# MINIMP3.net
KiCad netlist of a schematic drawn in Altium Designer
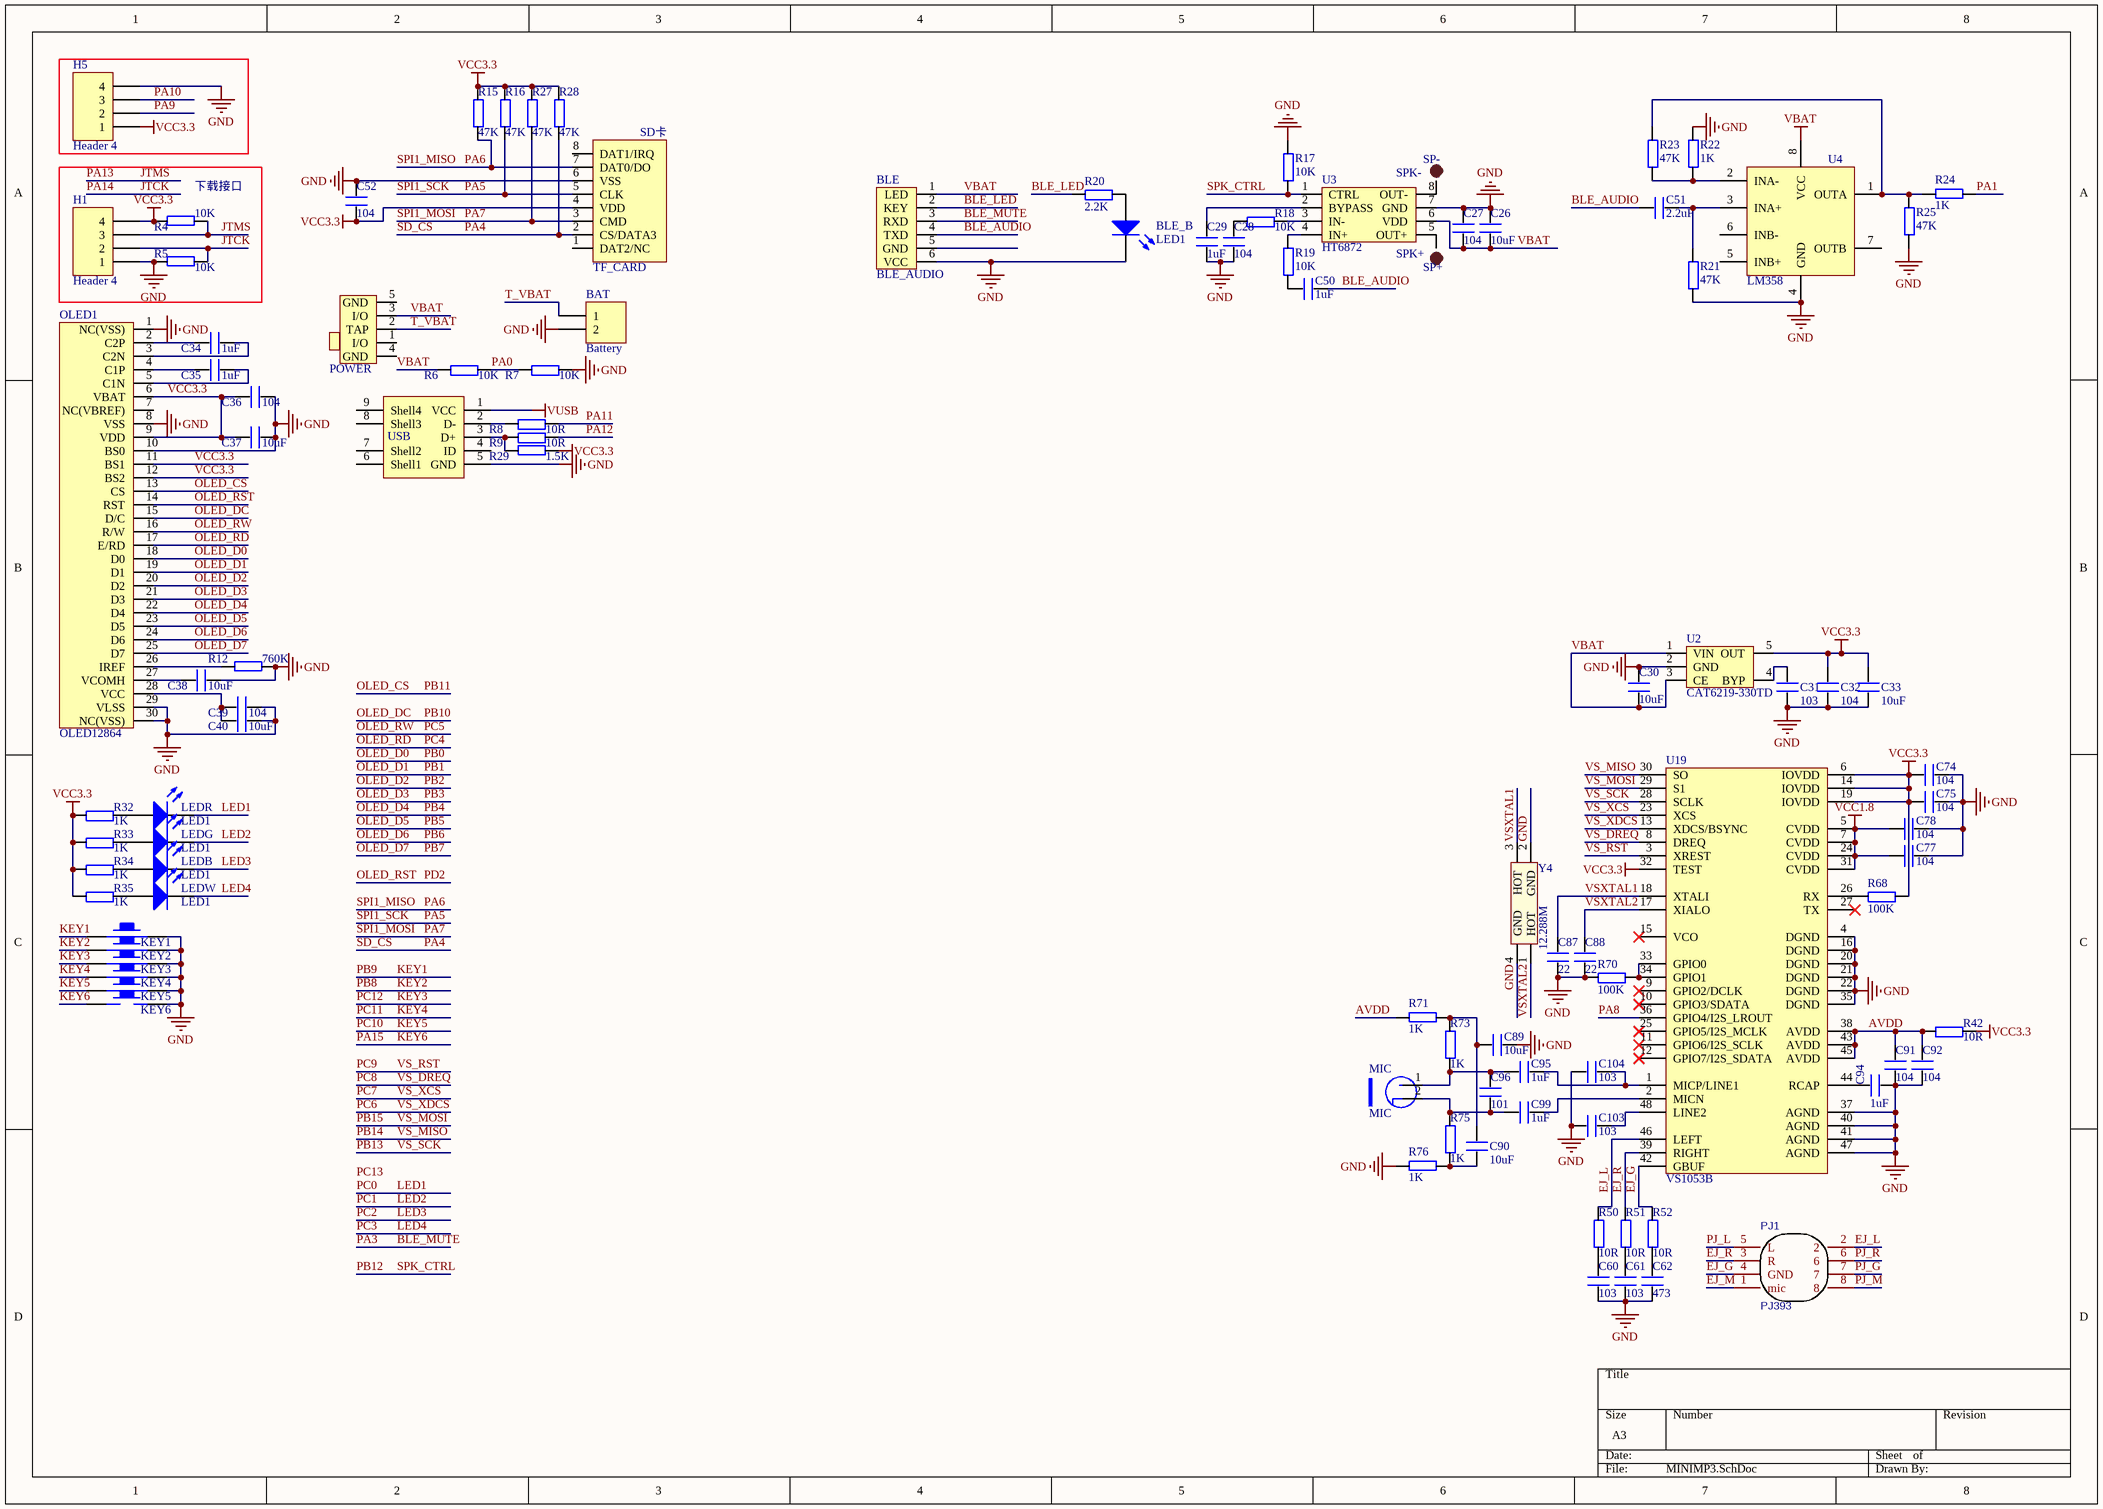
[diagram p0: MINIMP3.SchDoc]

(export (version "E")
  (design (tool "Eeschema 10.0.6"))
  (components
    (comp (ref "BAT")
      (value "Battery")
      (footprint "HDR2.54-LI-2P")
      (description "Header, 2-Pin")
      (fields (field (name "PUBLISHER") "Altium Limited"))
      (libsource (lib "WarShip V3 STM32103封装库") (part "Header 2"))
    )
    (comp (ref "BLE")
      (value "BLE_AUDIO")
      (footprint "HEAD6")
      (description "ATK-HC05")
      (libsource (lib "阿波罗STM32F4&F7&H7底板封装库") (part "ATK-HC05"))
    )
    (comp (ref "BLE_B")
      (value "LED1")
      (footprint "LED 0805B")
      (description "Typical RED, GREEN, YELLOW, AMBER GaAs LED")
      (fields (field (name "PUBLISHER") "Altium Limited"))
      (libsource (lib "阿波罗STM32F4&F7底板封装库") (part "LED2"))
    )
    (comp (ref "C26")
      (value "10uF")
      (footprint "C 0603_M")
      (libsource (lib "WarShip V3 STM32103封装库") (part "C"))
    )
    (comp (ref "C27")
      (value "104")
      (footprint "C 0603_M")
      (libsource (lib "WarShip V3 STM32103封装库") (part "C"))
    )
    (comp (ref "C28")
      (value "104")
      (footprint "C 0603_M")
      (libsource (lib "WarShip V3 STM32103封装库") (part "C"))
    )
    (comp (ref "C29")
      (value "1uF")
      (footprint "C 0603_M")
      (libsource (lib "WarShip V3 STM32103封装库") (part "C"))
    )
    (comp (ref "C30")
      (value "10uF")
      (footprint "C 0603_M")
      (libsource (lib "WarShip V3 STM32103封装库") (part "C"))
    )
    (comp (ref "C31")
      (value "103")
      (footprint "C 0603_M")
      (libsource (lib "WarShip V3 STM32103封装库") (part "C"))
    )
    (comp (ref "C32")
      (value "104")
      (footprint "C 0603_M")
      (libsource (lib "WarShip V3 STM32103封装库") (part "C"))
    )
    (comp (ref "C33")
      (value "10uF")
      (footprint "C 0603_M")
      (libsource (lib "WarShip V3 STM32103封装库") (part "C"))
    )
    (comp (ref "C34")
      (value "1uF")
      (footprint "C 0603_M")
      (libsource (lib "WarShip V3 STM32103封装库") (part "C"))
    )
    (comp (ref "C35")
      (value "1uF")
      (footprint "C 0603_M")
      (libsource (lib "WarShip V3 STM32103封装库") (part "C"))
    )
    (comp (ref "C36")
      (value "104")
      (footprint "C 0603_M")
      (libsource (lib "WarShip V3 STM32103封装库") (part "C"))
    )
    (comp (ref "C37")
      (value "10uF")
      (footprint "C 0603_M")
      (libsource (lib "WarShip V3 STM32103封装库") (part "C"))
    )
    (comp (ref "C38")
      (value "10uF")
      (footprint "C 0603_M")
      (libsource (lib "WarShip V3 STM32103封装库") (part "C"))
    )
    (comp (ref "C39")
      (value "104")
      (footprint "C 0603_M")
      (libsource (lib "WarShip V3 STM32103封装库") (part "C"))
    )
    (comp (ref "C40")
      (value "10uF")
      (footprint "C 0603_M")
      (libsource (lib "WarShip V3 STM32103封装库") (part "C"))
    )
    (comp (ref "C50") (value "1uF") (footprint "C 0603_M") (libsource (lib "MYCOMLIB") (part "C")))
    (comp (ref "C51") (value "2.2uF") (footprint "C 0603_M") (libsource (lib "MYCOMLIB") (part "C")))
    (comp (ref "C52")
      (value "104")
      (footprint "C 0603_M")
      (libsource (lib "WarShip V3 STM32103封装库") (part "C"))
    )
    (comp (ref "C60")
      (value "103")
      (footprint "C 0603_M")
      (libsource (lib "WarShip V3 STM32103封装库") (part "C"))
    )
    (comp (ref "C61")
      (value "103")
      (footprint "C 0603_M")
      (libsource (lib "WarShip V3 STM32103封装库") (part "C"))
    )
    (comp (ref "C62")
      (value "473")
      (footprint "C 0603_M")
      (libsource (lib "WarShip V3 STM32103封装库") (part "C"))
    )
    (comp (ref "C74") (value "104") (footprint "C 0603_M") (libsource (lib "ATK-VS1053 MP3") (part "C")))
    (comp (ref "C75") (value "104") (footprint "C 0603_M") (libsource (lib "ATK-VS1053 MP3") (part "C")))
    (comp (ref "C77") (value "104") (footprint "C 0603_M") (libsource (lib "ATK-VS1053 MP3") (part "C")))
    (comp (ref "C78") (value "104") (footprint "C 0603_M") (libsource (lib "ATK-VS1053 MP3") (part "C")))
    (comp (ref "C87") (value "22") (footprint "C 0603_M") (libsource (lib "ATK-VS1053 MP3") (part "C")))
    (comp (ref "C88") (value "22") (footprint "C 0603_M") (libsource (lib "ATK-VS1053 MP3") (part "C")))
    (comp (ref "C89")
      (value "10uF")
      (footprint "C 0805_M")
      (libsource (lib "WarShip V3 STM32103封装库") (part "C"))
    )
    (comp (ref "C90")
      (value "10uF")
      (footprint "C 0805_M")
      (libsource (lib "WarShip V3 STM32103封装库") (part "C"))
    )
    (comp (ref "C91") (value "104") (footprint "C 0603_M") (libsource (lib "ATK-VS1053 MP3") (part "C")))
    (comp (ref "C92") (value "104") (footprint "C 0603_M") (libsource (lib "ATK-VS1053 MP3") (part "C")))
    (comp (ref "C94") (value "1uF") (footprint "C 0603_M") (libsource (lib "ATK-VS1053 MP3") (part "C")))
    (comp (ref "C95")
      (value "1uF")
      (footprint "C 0603_M")
      (libsource (lib "WarShip V3 STM32103封装库") (part "C"))
    )
    (comp (ref "C96")
      (value "101")
      (footprint "C 0603_M")
      (libsource (lib "WarShip V3 STM32103封装库") (part "C"))
    )
    (comp (ref "C99")
      (value "1uF")
      (footprint "C 0603_M")
      (libsource (lib "WarShip V3 STM32103封装库") (part "C"))
    )
    (comp (ref "C103")
      (value "103")
      (footprint "C 0603_M")
      (libsource (lib "WarShip V3 STM32103封装库") (part "C"))
    )
    (comp (ref "C104")
      (value "103")
      (footprint "C 0603_M")
      (libsource (lib "WarShip V3 STM32103封装库") (part "C"))
    )
    (comp (ref "H1")
      (value "Header 4")
      (footprint "HDR2.54-LI-4P")
      (description "Header, 4-Pin")
      (fields (field (name "PUBLISHER") "Altium Limited"))
      (libsource (lib "WarShip V3 STM32103封装库") (part "Header 4"))
    )
    (comp (ref "H5")
      (value "Header 4")
      (footprint "HDR2.54-LI-4P")
      (description "Header, 4-Pin")
      (fields (field (name "PUBLISHER") "Altium Limited"))
      (libsource (lib "WarShip V3 STM32103封装库") (part "Header 4"))
    )
    (comp (ref "KEY1")
      (value "KEY_M")
      (footprint "KEY-SOP324225")
      (libsource (lib "WarShip V3 STM32103封装库") (part "KEY_M"))
    )
    (comp (ref "KEY2")
      (value "KEY_M")
      (footprint "KEY-SOP324225")
      (libsource (lib "WarShip V3 STM32103封装库") (part "KEY_M"))
    )
    (comp (ref "KEY3")
      (value "KEY_M")
      (footprint "KEY-SOP324225")
      (libsource (lib "WarShip V3 STM32103封装库") (part "KEY_M"))
    )
    (comp (ref "KEY4")
      (value "KEY_M")
      (footprint "KEY-SOP324225")
      (libsource (lib "WarShip V3 STM32103封装库") (part "KEY_M"))
    )
    (comp (ref "KEY5")
      (value "KEY_M")
      (footprint "KEY-SOP324225")
      (libsource (lib "WarShip V3 STM32103封装库") (part "KEY_M"))
    )
    (comp (ref "KEY6")
      (value "KEY_M")
      (footprint "KEY-SOP324225")
      (libsource (lib "WarShip V3 STM32103封装库") (part "KEY_M"))
    )
    (comp (ref "LEDB")
      (value "LED1")
      (footprint "LED 0805B")
      (description "Typical RED, GREEN, YELLOW, AMBER GaAs LED")
      (fields (field (name "PUBLISHER") "Altium Limited"))
      (libsource (lib "阿波罗STM32F4&F7底板封装库") (part "LED2"))
    )
    (comp (ref "LEDG")
      (value "LED1")
      (footprint "LED 0805B")
      (description "Typical RED, GREEN, YELLOW, AMBER GaAs LED")
      (fields (field (name "PUBLISHER") "Altium Limited"))
      (libsource (lib "阿波罗STM32F4&F7底板封装库") (part "LED2"))
    )
    (comp (ref "LEDR")
      (value "LED1")
      (footprint "LED 0805B")
      (description "Typical RED, GREEN, YELLOW, AMBER GaAs LED")
      (fields (field (name "PUBLISHER") "Altium Limited"))
      (libsource (lib "阿波罗STM32F4&F7底板封装库") (part "LED2"))
    )
    (comp (ref "LEDW")
      (value "LED1")
      (footprint "LED 0805B")
      (description "Typical RED, GREEN, YELLOW, AMBER GaAs LED")
      (fields (field (name "PUBLISHER") "Altium Limited"))
      (libsource (lib "阿波罗STM32F4&F7底板封装库") (part "LED2"))
    )
    (comp (ref "MIC") (value "MIC") (footprint "MIC-6022") (libsource (lib "ATK-VS1053 MP3") (part "MIC")))
    (comp (ref "OLED1")
      (value "OLED12864")
      (footprint "OLED_0.96")
      (libsource (lib "OLED模块封装库") (part "OLED12864"))
    )
    (comp (ref "PJ1")
      (value "PJ393")
      (footprint "PJ393")
      (fields
        (field (name "BOM_MANUFACTURER PART") "?")
        (field (name "CONTRIBUTOR") "infinite_possibilities")
      )
      (libsource (lib "PJ393") (part "PJ393"))
    )
    (comp (ref "POWER")
      (value "BUTTON_DIP3")
      (footprint "MSK-12C01-07")
      (description "拨动开关SS-12F44")
      (libsource (lib "Pandora_STM32L4_Board_V2.4") (part "BUTTON_DIP3"))
    )
    (comp (ref "R4")
      (value "10K")
      (footprint "R 0603_M")
      (libsource (lib "WarShip V3 STM32103封装库") (part "R"))
    )
    (comp (ref "R5")
      (value "10K")
      (footprint "R 0603_M")
      (libsource (lib "WarShip V3 STM32103封装库") (part "R"))
    )
    (comp (ref "R6")
      (value "10K")
      (footprint "R 0603_M")
      (libsource (lib "WarShip V3 STM32103封装库") (part "R"))
    )
    (comp (ref "R7")
      (value "10K")
      (footprint "R 0603_M")
      (libsource (lib "WarShip V3 STM32103封装库") (part "R"))
    )
    (comp (ref "R8")
      (value "10R")
      (footprint "R 0603_M")
      (libsource (lib "WarShip V3 STM32103封装库") (part "R"))
    )
    (comp (ref "R9")
      (value "10R")
      (footprint "R 0603_M")
      (libsource (lib "WarShip V3 STM32103封装库") (part "R"))
    )
    (comp (ref "R12")
      (value "760K")
      (footprint "R 0603_M")
      (libsource (lib "WarShip V3 STM32103封装库") (part "R"))
    )
    (comp (ref "R15")
      (value "47K")
      (footprint "R 0603_M")
      (libsource (lib "WarShip V3 STM32103封装库") (part "R"))
    )
    (comp (ref "R16")
      (value "47K")
      (footprint "R 0603_M")
      (libsource (lib "WarShip V3 STM32103封装库") (part "R"))
    )
    (comp (ref "R17") (value "10K") (footprint "R 0603_M") (libsource (lib "ALIENTEK_COMPONENT") (part "R")))
    (comp (ref "R18") (value "10K") (footprint "R 0603_M") (libsource (lib "ALIENTEK_COMPONENT") (part "R")))
    (comp (ref "R19") (value "10K") (footprint "R 0603_M") (libsource (lib "ALIENTEK_COMPONENT") (part "R")))
    (comp (ref "R20")
      (value "2.2K")
      (footprint "R 0603_M")
      (libsource (lib "WarShip V3 STM32103封装库") (part "R"))
    )
    (comp (ref "R21") (value "47K") (footprint "R 0603_M") (libsource (lib "ALIENTEK_COMPONENT") (part "R")))
    (comp (ref "R22") (value "1K") (footprint "R 0603_M") (libsource (lib "ALIENTEK_COMPONENT") (part "R")))
    (comp (ref "R23") (value "47K") (footprint "R 0603_M") (libsource (lib "ALIENTEK_COMPONENT") (part "R")))
    (comp (ref "R24") (value "1K") (footprint "R 0603_M") (libsource (lib "ALIENTEK_COMPONENT") (part "R")))
    (comp (ref "R25") (value "47K") (footprint "R 0603_M") (libsource (lib "ALIENTEK_COMPONENT") (part "R")))
    (comp (ref "R27")
      (value "47K")
      (footprint "R 0603_M")
      (libsource (lib "WarShip V3 STM32103封装库") (part "R"))
    )
    (comp (ref "R28")
      (value "47K")
      (footprint "R 0603_M")
      (libsource (lib "WarShip V3 STM32103封装库") (part "R"))
    )
    (comp (ref "R29")
      (value "1.5K")
      (footprint "R 0603_M")
      (libsource (lib "WarShip V3 STM32103封装库") (part "R"))
    )
    (comp (ref "R32")
      (value "1K")
      (footprint "R 0603_M")
      (libsource (lib "WarShip V3 STM32103封装库") (part "R"))
    )
    (comp (ref "R33")
      (value "1K")
      (footprint "R 0603_M")
      (libsource (lib "WarShip V3 STM32103封装库") (part "R"))
    )
    (comp (ref "R34")
      (value "1K")
      (footprint "R 0603_M")
      (libsource (lib "WarShip V3 STM32103封装库") (part "R"))
    )
    (comp (ref "R35")
      (value "1K")
      (footprint "R 0603_M")
      (libsource (lib "WarShip V3 STM32103封装库") (part "R"))
    )
    (comp (ref "R42") (value "10R") (footprint "R 0603_M") (libsource (lib "ATK-VS1053 MP3") (part "R")))
    (comp (ref "R50")
      (value "10R")
      (footprint "R 0603_M")
      (libsource (lib "WarShip V3 STM32103封装库") (part "R"))
    )
    (comp (ref "R51")
      (value "10R")
      (footprint "R 0603_M")
      (libsource (lib "WarShip V3 STM32103封装库") (part "R"))
    )
    (comp (ref "R52")
      (value "10R")
      (footprint "R 0603_M")
      (libsource (lib "WarShip V3 STM32103封装库") (part "R"))
    )
    (comp (ref "R68") (value "100K") (footprint "R 0603_M") (libsource (lib "ATK-VS1053 MP3") (part "R")))
    (comp (ref "R70") (value "100K") (footprint "R 0603_M") (libsource (lib "ATK-VS1053 MP3") (part "R")))
    (comp (ref "R71")
      (value "1K")
      (footprint "R 0603_M")
      (libsource (lib "WarShip V3 STM32103封装库") (part "R"))
    )
    (comp (ref "R73")
      (value "1K")
      (footprint "R 0603_M")
      (libsource (lib "WarShip V3 STM32103封装库") (part "R"))
    )
    (comp (ref "R75")
      (value "1K")
      (footprint "R 0603_M")
      (libsource (lib "WarShip V3 STM32103封装库") (part "R"))
    )
    (comp (ref "R76")
      (value "1K")
      (footprint "R 0603_M")
      (libsource (lib "WarShip V3 STM32103封装库") (part "R"))
    )
    (comp (ref "SP+")
      (value "SPK+")
      (footprint "TP-1.5")
      (description "测试点")
      (libsource (lib "ALIENTEK_COMPONENT") (part "TEST-POINT"))
    )
    (comp (ref "SP-")
      (value "SPK-")
      (footprint "TP-1.5")
      (description "测试点")
      (libsource (lib "ALIENTEK_COMPONENT") (part "TEST-POINT"))
    )
    (comp (ref "TF_CARD")
      (value "SD-MICRO-TF")
      (footprint "SD-MICRO-TF")
      (description "SD,MICRO,TF")
      (libsource (lib "Pandora_STM32L4_Board_V2.4") (part "SD-MICRO-TF"))
    )
    (comp (ref "U2")
      (value "CAT6219-330TD")
      (footprint "SOT23-5N")
      (description "3.3V 500mA LDO")
      (libsource (lib "STM32H743核心板封装库") (part "CAT6219-330TD"))
    )
    (comp (ref "U3")
      (value "HT6872")
      (footprint "SOP8_N")
      (description "HT6871")
      (libsource (lib "WarShip V3 STM32103封装库") (part "HT6871"))
    )
    (comp (ref "U4") (value "LM358") (footprint "SOP8_N") (libsource (lib "tp4056") (part "Component_2")))
    (comp (ref "U19")
      (value "VS1053B")
      (footprint "LQFP-48N")
      (libsource (lib "ATK-VS1053 MP3") (part "VS1053"))
    )
    (comp (ref "USB")
      (value "J-MICRO-USB-5S")
      (footprint "USB-AB-5S")
      (description "Micro USB 5.9有柱脚长1.25加长针")
      (libsource (lib "Pandora_STM32L4_Board_V2.4") (part "J-MICRO-USB-5S"))
    )
    (comp (ref "Y4")
      (value "12.288M")
      (footprint "OSC 3225-4P")
      (description "3225贴片无源晶振")
      (libsource (lib "STM32F767核心板封装库") (part "XTAL_3225"))
    )
  )
  (nets
    (net (code "1") (name "/AVDD") (class "Default")
      (node (ref "C91") (pin "2") (pintype "passive"))
      (node (ref "C92") (pin "2") (pintype "passive"))
      (node (ref "R42") (pin "1") (pintype "passive"))
      (node (ref "R71") (pin "2") (pintype "passive"))
      (node (ref "U19") (pin "38") (pinfunction "AVDD_38") (pintype "passive"))
      (node (ref "U19") (pin "43") (pinfunction "AVDD_43") (pintype "passive"))
      (node (ref "U19") (pin "45") (pinfunction "AVDD_45") (pintype "passive"))
    )
    (net (code "2") (name "/BLE_AUDIO") (class "Default")
      (node (ref "BLE") (pin "4") (pinfunction "TXD_4") (pintype "passive"))
      (node (ref "C50") (pin "2") (pintype "passive"))
      (node (ref "C51") (pin "1") (pintype "passive"))
    )
    (net (code "3") (name "/BLE_LED") (class "Default")
      (node (ref "BLE") (pin "2") (pinfunction "KEY_2") (pintype "passive"))
      (node (ref "R20") (pin "1") (pintype "passive"))
    )
    (net (code "4") (name "/BLE_MUTE") (class "Default")
      (node (ref "BLE") (pin "3") (pinfunction "RXD_3") (pintype "passive"))
    )
    (net (code "5") (name "/EJ_G") (class "Default")
      (node (ref "PJ1") (pin "4") (pinfunction "GND_4") (pintype "passive"))
      (node (ref "R52") (pin "2") (pintype "passive"))
      (node (ref "U19") (pin "42") (pinfunction "GBUF_42") (pintype "passive"))
    )
    (net (code "6") (name "/EJ_L") (class "Default")
      (node (ref "PJ1") (pin "2") (pinfunction "2_2") (pintype "passive"))
      (node (ref "R50") (pin "2") (pintype "passive"))
      (node (ref "U19") (pin "46") (pinfunction "LEFT_46") (pintype "passive"))
    )
    (net (code "7") (name "/EJ_M") (class "Default")
      (node (ref "PJ1") (pin "1") (pinfunction "mic_1") (pintype "passive"))
    )
    (net (code "8") (name "/EJ_R") (class "Default")
      (node (ref "PJ1") (pin "3") (pinfunction "R_3") (pintype "passive"))
      (node (ref "R51") (pin "2") (pintype "passive"))
      (node (ref "U19") (pin "39") (pinfunction "RIGHT_39") (pintype "passive"))
    )
    (net (code "9") (name "/JTCK") (class "Default")
      (node (ref "H1") (pin "2") (pinfunction "2_2") (pintype "passive"))
      (node (ref "R5") (pin "1") (pintype "passive"))
    )
    (net (code "10") (name "/JTMS") (class "Default")
      (node (ref "H1") (pin "3") (pinfunction "3_3") (pintype "passive"))
      (node (ref "R4") (pin "1") (pintype "passive"))
    )
    (net (code "11") (name "/KEY1") (class "Default")
      (node (ref "KEY1") (pin "1") (pinfunction "1_1") (pintype "passive"))
    )
    (net (code "12") (name "/KEY2") (class "Default")
      (node (ref "KEY2") (pin "1") (pinfunction "1_1") (pintype "passive"))
    )
    (net (code "13") (name "/KEY3") (class "Default")
      (node (ref "KEY3") (pin "1") (pinfunction "1_1") (pintype "passive"))
    )
    (net (code "14") (name "/KEY4") (class "Default")
      (node (ref "KEY4") (pin "1") (pinfunction "1_1") (pintype "passive"))
    )
    (net (code "15") (name "/KEY5") (class "Default")
      (node (ref "KEY5") (pin "1") (pinfunction "1_1") (pintype "passive"))
    )
    (net (code "16") (name "/KEY6") (class "Default")
      (node (ref "KEY6") (pin "1") (pinfunction "1_1") (pintype "passive"))
    )
    (net (code "17") (name "/LED1") (class "Default")
      (node (ref "LEDR") (pin "2") (pinfunction "K_2") (pintype "passive"))
    )
    (net (code "18") (name "/LED2") (class "Default")
      (node (ref "LEDG") (pin "2") (pinfunction "K_2") (pintype "passive"))
    )
    (net (code "19") (name "/LED3") (class "Default")
      (node (ref "LEDB") (pin "2") (pinfunction "K_2") (pintype "passive"))
    )
    (net (code "20") (name "/LED4") (class "Default")
      (node (ref "LEDW") (pin "2") (pinfunction "K_2") (pintype "passive"))
    )
    (net (code "21") (name "/OLED_CS") (class "Default")
      (node (ref "OLED1") (pin "13") (pinfunction "CS_13") (pintype "passive"))
    )
    (net (code "22") (name "/OLED_D0") (class "Default")
      (node (ref "OLED1") (pin "18") (pinfunction "D0_18") (pintype "passive"))
    )
    (net (code "23") (name "/OLED_D1") (class "Default")
      (node (ref "OLED1") (pin "19") (pinfunction "D1_19") (pintype "passive"))
    )
    (net (code "24") (name "/OLED_D2") (class "Default")
      (node (ref "OLED1") (pin "20") (pinfunction "D2_20") (pintype "passive"))
    )
    (net (code "25") (name "/OLED_D3") (class "Default")
      (node (ref "OLED1") (pin "21") (pinfunction "D3_21") (pintype "passive"))
    )
    (net (code "26") (name "/OLED_D4") (class "Default")
      (node (ref "OLED1") (pin "22") (pinfunction "D4_22") (pintype "passive"))
    )
    (net (code "27") (name "/OLED_D5") (class "Default")
      (node (ref "OLED1") (pin "23") (pinfunction "D5_23") (pintype "passive"))
    )
    (net (code "28") (name "/OLED_D6") (class "Default")
      (node (ref "OLED1") (pin "24") (pinfunction "D6_24") (pintype "passive"))
    )
    (net (code "29") (name "/OLED_D7") (class "Default")
      (node (ref "OLED1") (pin "25") (pinfunction "D7_25") (pintype "passive"))
    )
    (net (code "30") (name "/OLED_DC") (class "Default")
      (node (ref "OLED1") (pin "15") (pinfunction "D/C_15") (pintype "passive"))
    )
    (net (code "31") (name "/OLED_RD") (class "Default")
      (node (ref "OLED1") (pin "17") (pinfunction "E/RD_17") (pintype "passive"))
    )
    (net (code "32") (name "/OLED_RST") (class "Default")
      (node (ref "OLED1") (pin "14") (pinfunction "RST_14") (pintype "passive"))
    )
    (net (code "33") (name "/OLED_RW") (class "Default")
      (node (ref "OLED1") (pin "16") (pinfunction "R/W_16") (pintype "passive"))
    )
    (net (code "34") (name "/PA0") (class "Default")
      (node (ref "R6") (pin "2") (pintype "passive"))
      (node (ref "R7") (pin "1") (pintype "passive"))
    )
    (net (code "35") (name "/PA1") (class "Default") (node (ref "R24") (pin "1") (pintype "passive")))
    (net (code "36") (name "/PA4") (class "Default")
      (node (ref "R28") (pin "1") (pintype "passive"))
      (node (ref "TF_CARD") (pin "2") (pinfunction "CS/DATA3_2") (pintype "passive"))
    )
    (net (code "37") (name "/PA5") (class "Default")
      (node (ref "R16") (pin "1") (pintype "passive"))
      (node (ref "TF_CARD") (pin "5") (pinfunction "CLK_5") (pintype "passive"))
    )
    (net (code "38") (name "/PA6") (class "Default")
      (node (ref "R15") (pin "1") (pintype "passive"))
      (node (ref "TF_CARD") (pin "7") (pinfunction "DAT0/DO_7") (pintype "passive"))
    )
    (net (code "39") (name "/PA7") (class "Default")
      (node (ref "R27") (pin "1") (pintype "passive"))
      (node (ref "TF_CARD") (pin "3") (pinfunction "CMD_3") (pintype "passive"))
    )
    (net (code "40") (name "/PA8") (class "Default")
      (node (ref "U19") (pin "36") (pinfunction "GPIO4/I2S_LROUT_36") (pintype "passive"))
    )
    (net (code "41") (name "/PA9") (class "Default")
      (node (ref "H5") (pin "2") (pinfunction "2_2") (pintype "passive"))
    )
    (net (code "42") (name "/PA10") (class "Default")
      (node (ref "H5") (pin "3") (pinfunction "3_3") (pintype "passive"))
    )
    (net (code "43") (name "/PA11") (class "Default") (node (ref "R8") (pin "2") (pintype "passive")))
    (net (code "44") (name "/PA12") (class "Default") (node (ref "R9") (pin "2") (pintype "passive")))
    (net (code "45") (name "/PB12") (class "Default")
      (node (ref "R17") (pin "1") (pintype "passive"))
      (node (ref "U3") (pin "1") (pinfunction "CTRL_1") (pintype "passive"))
    )
    (net (code "46") (name "/PB13") (class "Default")
      (node (ref "U19") (pin "28") (pinfunction "SCLK_28") (pintype "passive"))
    )
    (net (code "47") (name "/PB14") (class "Default")
      (node (ref "U19") (pin "30") (pinfunction "SO_30") (pintype "passive"))
    )
    (net (code "48") (name "/PB15") (class "Default")
      (node (ref "U19") (pin "29") (pinfunction "S1_29") (pintype "passive"))
    )
    (net (code "49") (name "/PC6") (class "Default")
      (node (ref "U19") (pin "13") (pinfunction "XDCS/BSYNC_13") (pintype "passive"))
    )
    (net (code "50") (name "/PC7") (class "Default")
      (node (ref "U19") (pin "23") (pinfunction "XCS_23") (pintype "passive"))
    )
    (net (code "51") (name "/PC8") (class "Default")
      (node (ref "U19") (pin "8") (pinfunction "DREQ_8") (pintype "passive"))
    )
    (net (code "52") (name "/PC9") (class "Default")
      (node (ref "U19") (pin "3") (pinfunction "XREST_3") (pintype "passive"))
    )
    (net (code "54") (name "/PJ_G") (class "Default")
      (node (ref "PJ1") (pin "7") (pinfunction "7_7") (pintype "passive"))
    )
    (net (code "55") (name "/PJ_L") (class "Default")
      (node (ref "PJ1") (pin "5") (pinfunction "L_5") (pintype "passive"))
    )
    (net (code "56") (name "/PJ_M") (class "Default")
      (node (ref "PJ1") (pin "8") (pinfunction "8_8") (pintype "passive"))
    )
    (net (code "57") (name "/PJ_R") (class "Default")
      (node (ref "PJ1") (pin "6") (pinfunction "6_6") (pintype "passive"))
    )
    (net (code "58") (name "/T_VBAT") (class "Default")
      (node (ref "BAT") (pin "1") (pinfunction "1_1") (pintype "passive"))
      (node (ref "POWER") (pin "2") (pinfunction "TAP_2") (pintype "passive"))
    )
    (net (code "59") (name "/VSXTAL1") (class "Default")
      (node (ref "C87") (pin "2") (pintype "passive"))
      (node (ref "U19") (pin "18") (pinfunction "XTALI_18") (pintype "passive"))
      (node (ref "Y4") (pin "3") (pinfunction "HOT_3") (pintype "passive"))
    )
    (net (code "60") (name "/VSXTAL2") (class "Default")
      (node (ref "C88") (pin "2") (pintype "passive"))
      (node (ref "U19") (pin "17") (pinfunction "XIALO_17") (pintype "passive"))
      (node (ref "Y4") (pin "1") (pinfunction "HOT_1") (pintype "passive"))
    )
    (net (code "61") (name "GND") (class "Default")
      (node (ref "BAT") (pin "2") (pinfunction "2_2") (pintype "passive"))
      (node (ref "BLE") (pin "6") (pinfunction "VCC_6") (pintype "passive"))
      (node (ref "BLE_B") (pin "2") (pinfunction "K_2") (pintype "passive"))
      (node (ref "C103") (pin "2") (pintype "passive"))
      (node (ref "C104") (pin "1") (pintype "passive"))
      (node (ref "C26") (pin "2") (pintype "passive"))
      (node (ref "C27") (pin "2") (pintype "passive"))
      (node (ref "C28") (pin "1") (pintype "passive"))
      (node (ref "C29") (pin "1") (pintype "passive"))
      (node (ref "C30") (pin "2") (pintype "passive"))
      (node (ref "C31") (pin "1") (pintype "passive"))
      (node (ref "C32") (pin "1") (pintype "passive"))
      (node (ref "C33") (pin "1") (pintype "passive"))
      (node (ref "C36") (pin "1") (pintype "passive"))
      (node (ref "C37") (pin "1") (pintype "passive"))
      (node (ref "C38") (pin "1") (pintype "passive"))
      (node (ref "C39") (pin "1") (pintype "passive"))
      (node (ref "C40") (pin "1") (pintype "passive"))
      (node (ref "C52") (pin "2") (pintype "passive"))
      (node (ref "C60") (pin "1") (pintype "passive"))
      (node (ref "C61") (pin "1") (pintype "passive"))
      (node (ref "C62") (pin "1") (pintype "passive"))
      (node (ref "C74") (pin "2") (pintype "passive"))
      (node (ref "C75") (pin "1") (pintype "passive"))
      (node (ref "C77") (pin "2") (pintype "passive"))
      (node (ref "C78") (pin "2") (pintype "passive"))
      (node (ref "C87") (pin "1") (pintype "passive"))
      (node (ref "C88") (pin "1") (pintype "passive"))
      (node (ref "C89") (pin "1") (pintype "passive"))
      (node (ref "C91") (pin "1") (pintype "passive"))
      (node (ref "C92") (pin "1") (pintype "passive"))
      (node (ref "C94") (pin "2") (pintype "passive"))
      (node (ref "H1") (pin "1") (pinfunction "1_1") (pintype "passive"))
      (node (ref "H5") (pin "4") (pinfunction "4_4") (pintype "passive"))
      (node (ref "KEY1") (pin "2") (pinfunction "2_2") (pintype "passive"))
      (node (ref "KEY2") (pin "2") (pinfunction "2_2") (pintype "passive"))
      (node (ref "KEY3") (pin "2") (pinfunction "2_2") (pintype "passive"))
      (node (ref "KEY4") (pin "2") (pinfunction "2_2") (pintype "passive"))
      (node (ref "KEY5") (pin "2") (pinfunction "2_2") (pintype "passive"))
      (node (ref "KEY6") (pin "2") (pinfunction "2_2") (pintype "passive"))
      (node (ref "OLED1") (pin "1") (pinfunction "NC(VSS)_1") (pintype "passive"))
      (node (ref "OLED1") (pin "10") (pinfunction "BS0_10") (pintype "passive"))
      (node (ref "OLED1") (pin "29") (pinfunction "VLSS_29") (pintype "passive"))
      (node (ref "OLED1") (pin "30") (pinfunction "NC(VSS)_30") (pintype "passive"))
      (node (ref "OLED1") (pin "8") (pinfunction "VSS_8") (pintype "passive"))
      (node (ref "R12") (pin "1") (pintype "passive"))
      (node (ref "R17") (pin "2") (pintype "passive"))
      (node (ref "R21") (pin "1") (pintype "passive"))
      (node (ref "R22") (pin "2") (pintype "passive"))
      (node (ref "R25") (pin "1") (pintype "passive"))
      (node (ref "R5") (pin "2") (pintype "passive"))
      (node (ref "R7") (pin "2") (pintype "passive"))
      (node (ref "R70") (pin "1") (pintype "passive"))
      (node (ref "R76") (pin "2") (pintype "passive"))
      (node (ref "TF_CARD") (pin "6") (pinfunction "VSS_6") (pintype "passive"))
      (node (ref "U19") (pin "16") (pinfunction "DGND_16") (pintype "passive"))
      (node (ref "U19") (pin "20") (pinfunction "DGND_20") (pintype "passive"))
      (node (ref "U19") (pin "21") (pinfunction "DGND_21") (pintype "passive"))
      (node (ref "U19") (pin "22") (pinfunction "DGND_22") (pintype "passive"))
      (node (ref "U19") (pin "35") (pinfunction "DGND_35") (pintype "passive"))
      (node (ref "U19") (pin "37") (pinfunction "AGND_37") (pintype "passive"))
      (node (ref "U19") (pin "4") (pinfunction "DGND_4") (pintype "passive"))
      (node (ref "U19") (pin "40") (pinfunction "AGND_40") (pintype "passive"))
      (node (ref "U19") (pin "41") (pinfunction "AGND_41") (pintype "passive"))
      (node (ref "U19") (pin "47") (pinfunction "AGND_47") (pintype "passive"))
      (node (ref "U2") (pin "2") (pinfunction "GND_2") (pintype "passive"))
      (node (ref "U3") (pin "7") (pinfunction "GND_7") (pintype "passive"))
      (node (ref "U4") (pin "4") (pinfunction "GND_4") (pintype "passive"))
      (node (ref "USB") (pin "5") (pinfunction "GND_5") (pintype "passive"))
      (node (ref "Y4") (pin "2") (pinfunction "GND_2") (pintype "passive"))
      (node (ref "Y4") (pin "4") (pinfunction "GND_4") (pintype "passive"))
    )
    (net (code "62") (name "Net-(BLE_B-A)") (class "Default")
      (node (ref "BLE_B") (pin "1") (pinfunction "A_1") (pintype "passive"))
      (node (ref "R20") (pin "2") (pintype "passive"))
    )
    (net (code "63") (name "Net-(C28-Pad2)") (class "Default")
      (node (ref "C28") (pin "2") (pintype "passive"))
      (node (ref "R18") (pin "1") (pintype "passive"))
    )
    (net (code "64") (name "Net-(C50-Pad1)") (class "Default")
      (node (ref "C50") (pin "1") (pintype "passive"))
      (node (ref "R19") (pin "1") (pintype "passive"))
    )
    (net (code "65") (name "Net-(C60-Pad2)") (class "Default")
      (node (ref "C60") (pin "2") (pintype "passive"))
      (node (ref "R50") (pin "1") (pintype "passive"))
    )
    (net (code "66") (name "Net-(C61-Pad2)") (class "Default")
      (node (ref "C61") (pin "2") (pintype "passive"))
      (node (ref "R51") (pin "1") (pintype "passive"))
    )
    (net (code "67") (name "Net-(C62-Pad2)") (class "Default")
      (node (ref "C62") (pin "2") (pintype "passive"))
      (node (ref "R52") (pin "1") (pintype "passive"))
    )
    (net (code "68") (name "Net-(C89-Pad2)") (class "Default")
      (node (ref "C89") (pin "2") (pintype "passive"))
      (node (ref "C90") (pin "2") (pintype "passive"))
      (node (ref "R71") (pin "1") (pintype "passive"))
      (node (ref "R73") (pin "2") (pintype "passive"))
    )
    (net (code "69") (name "Net-(C90-Pad1)") (class "Default")
      (node (ref "C90") (pin "1") (pintype "passive"))
      (node (ref "R75") (pin "1") (pintype "passive"))
      (node (ref "R76") (pin "1") (pintype "passive"))
    )
    (net (code "70") (name "Net-(LEDB-A)") (class "Default")
      (node (ref "LEDB") (pin "1") (pinfunction "A_1") (pintype "passive"))
      (node (ref "R34") (pin "2") (pintype "passive"))
    )
    (net (code "71") (name "Net-(LEDG-A)") (class "Default")
      (node (ref "LEDG") (pin "1") (pinfunction "A_1") (pintype "passive"))
      (node (ref "R33") (pin "2") (pintype "passive"))
    )
    (net (code "72") (name "Net-(LEDR-A)") (class "Default")
      (node (ref "LEDR") (pin "1") (pinfunction "A_1") (pintype "passive"))
      (node (ref "R32") (pin "2") (pintype "passive"))
    )
    (net (code "73") (name "Net-(LEDW-A)") (class "Default")
      (node (ref "LEDW") (pin "1") (pinfunction "A_1") (pintype "passive"))
      (node (ref "R35") (pin "2") (pintype "passive"))
    )
    (net (code "74") (name "Net-(MIC-GND)") (class "Default")
      (node (ref "C96") (pin "1") (pintype "passive"))
      (node (ref "C99") (pin "2") (pintype "passive"))
      (node (ref "MIC") (pin "2") (pinfunction "GND_2") (pintype "passive"))
      (node (ref "R75") (pin "2") (pintype "passive"))
    )
    (net (code "75") (name "Net-(MIC-VCC)") (class "Default")
      (node (ref "C95") (pin "1") (pintype "passive"))
      (node (ref "C96") (pin "2") (pintype "passive"))
      (node (ref "MIC") (pin "1") (pinfunction "VCC_1") (pintype "passive"))
      (node (ref "R73") (pin "1") (pintype "passive"))
    )
    (net (code "76") (name "Net-(OLED1-C1N)") (class "Default")
      (node (ref "C35") (pin "1") (pintype "passive"))
      (node (ref "OLED1") (pin "5") (pinfunction "C1N_5") (pintype "passive"))
    )
    (net (code "77") (name "Net-(OLED1-C1P)") (class "Default")
      (node (ref "C35") (pin "2") (pintype "passive"))
      (node (ref "OLED1") (pin "4") (pinfunction "C1P_4") (pintype "passive"))
    )
    (net (code "78") (name "Net-(OLED1-C2N)") (class "Default")
      (node (ref "C34") (pin "1") (pintype "passive"))
      (node (ref "OLED1") (pin "3") (pinfunction "C2N_3") (pintype "passive"))
    )
    (net (code "79") (name "Net-(OLED1-C2P)") (class "Default")
      (node (ref "C34") (pin "2") (pintype "passive"))
      (node (ref "OLED1") (pin "2") (pinfunction "C2P_2") (pintype "passive"))
    )
    (net (code "80") (name "Net-(OLED1-IREF)") (class "Default")
      (node (ref "OLED1") (pin "26") (pinfunction "IREF_26") (pintype "passive"))
      (node (ref "R12") (pin "2") (pintype "passive"))
    )
    (net (code "81") (name "Net-(OLED1-VCC)") (class "Default")
      (node (ref "C39") (pin "2") (pintype "passive"))
      (node (ref "C40") (pin "2") (pintype "passive"))
      (node (ref "OLED1") (pin "28") (pinfunction "VCC_28") (pintype "passive"))
    )
    (net (code "82") (name "Net-(OLED1-VCOMH)") (class "Default")
      (node (ref "C38") (pin "2") (pintype "passive"))
      (node (ref "OLED1") (pin "27") (pinfunction "VCOMH_27") (pintype "passive"))
    )
    (net (code "83") (name "Net-(U2-BYP)") (class "Default")
      (node (ref "C31") (pin "2") (pintype "passive"))
      (node (ref "U2") (pin "4") (pinfunction "BYP_4") (pintype "passive"))
    )
    (net (code "84") (name "Net-(U3-BYPASS)") (class "Default")
      (node (ref "C29") (pin "2") (pintype "passive"))
      (node (ref "U3") (pin "2") (pinfunction "BYPASS_2") (pintype "passive"))
    )
    (net (code "85") (name "Net-(U3-IN+)") (class "Default")
      (node (ref "R19") (pin "2") (pintype "passive"))
      (node (ref "U3") (pin "4") (pinfunction "IN+_4") (pintype "passive"))
    )
    (net (code "86") (name "Net-(U3-IN-)") (class "Default")
      (node (ref "R18") (pin "2") (pintype "passive"))
      (node (ref "U3") (pin "3") (pinfunction "IN-_3") (pintype "passive"))
    )
    (net (code "87") (name "Net-(U3-OUT+)") (class "Default")
      (node (ref "SP+") (pin "1") (pinfunction "1_1") (pintype "passive"))
      (node (ref "U3") (pin "5") (pinfunction "OUT+_5") (pintype "passive"))
    )
    (net (code "88") (name "Net-(U3-OUT-)") (class "Default")
      (node (ref "SP-") (pin "1") (pinfunction "1_1") (pintype "passive"))
      (node (ref "U3") (pin "8") (pinfunction "OUT-_8") (pintype "passive"))
    )
    (net (code "89") (name "Net-(U4-INA+)") (class "Default")
      (node (ref "C51") (pin "2") (pintype "passive"))
      (node (ref "R21") (pin "2") (pintype "passive"))
      (node (ref "U4") (pin "3") (pinfunction "INA+_3") (pintype "passive"))
    )
    (net (code "90") (name "Net-(U4-INA-)") (class "Default")
      (node (ref "R22") (pin "1") (pintype "passive"))
      (node (ref "R23") (pin "1") (pintype "passive"))
      (node (ref "U4") (pin "2") (pinfunction "INA-_2") (pintype "passive"))
    )
    (net (code "91") (name "Net-(U4-OUTA)") (class "Default")
      (node (ref "R23") (pin "2") (pintype "passive"))
      (node (ref "R24") (pin "2") (pintype "passive"))
      (node (ref "R25") (pin "2") (pintype "passive"))
      (node (ref "U4") (pin "1") (pinfunction "OUTA_1") (pintype "passive"))
    )
    (net (code "92") (name "Net-(U19-GPIO0)") (class "Default")
      (node (ref "R70") (pin "2") (pintype "passive"))
      (node (ref "U19") (pin "33") (pinfunction "GPIO0_33") (pintype "passive"))
      (node (ref "U19") (pin "34") (pinfunction "GPIO1_34") (pintype "passive"))
    )
    (net (code "93") (name "Net-(U19-LINE2)") (class "Default")
      (node (ref "C103") (pin "1") (pintype "passive"))
      (node (ref "U19") (pin "48") (pinfunction "LINE2_48") (pintype "passive"))
    )
    (net (code "94") (name "Net-(U19-MICN)") (class "Default")
      (node (ref "C99") (pin "1") (pintype "passive"))
      (node (ref "U19") (pin "2") (pinfunction "MICN_2") (pintype "passive"))
    )
    (net (code "95") (name "Net-(U19-MICP{slash}LINE1)") (class "Default")
      (node (ref "C104") (pin "2") (pintype "passive"))
      (node (ref "C95") (pin "2") (pintype "passive"))
      (node (ref "U19") (pin "1") (pinfunction "MICP/LINE1_1") (pintype "passive"))
    )
    (net (code "96") (name "Net-(U19-RCAP)") (class "Default")
      (node (ref "C94") (pin "1") (pintype "passive"))
      (node (ref "U19") (pin "44") (pinfunction "RCAP_44") (pintype "passive"))
    )
    (net (code "97") (name "Net-(U19-RX)") (class "Default")
      (node (ref "R68") (pin "1") (pintype "passive"))
      (node (ref "U19") (pin "26") (pinfunction "RX_26") (pintype "passive"))
    )
    (net (code "98") (name "Net-(USB-D+)") (class "Default")
      (node (ref "R29") (pin "2") (pintype "passive"))
      (node (ref "R9") (pin "1") (pintype "passive"))
      (node (ref "USB") (pin "3") (pinfunction "D+_3") (pintype "passive"))
    )
    (net (code "99") (name "Net-(USB-D-)") (class "Default")
      (node (ref "R8") (pin "1") (pintype "passive"))
      (node (ref "USB") (pin "2") (pinfunction "D-_2") (pintype "passive"))
    )
    (net (code "100") (name "VBAT") (class "Default")
      (node (ref "BLE") (pin "1") (pinfunction "LED_1") (pintype "passive"))
      (node (ref "C26") (pin "1") (pintype "passive"))
      (node (ref "C27") (pin "1") (pintype "passive"))
      (node (ref "C30") (pin "1") (pintype "passive"))
      (node (ref "POWER") (pin "3") (pinfunction "I/O_3") (pintype "passive"))
      (node (ref "R6") (pin "1") (pintype "passive"))
      (node (ref "U2") (pin "1") (pinfunction "VIN_1") (pintype "passive"))
      (node (ref "U2") (pin "3") (pinfunction "CE_3") (pintype "passive"))
      (node (ref "U3") (pin "6") (pinfunction "VDD_6") (pintype "passive"))
      (node (ref "U4") (pin "8") (pinfunction "VCC_8") (pintype "passive"))
    )
    (net (code "101") (name "VCC1.8") (class "Default")
      (node (ref "C77") (pin "1") (pintype "passive"))
      (node (ref "C78") (pin "1") (pintype "passive"))
      (node (ref "U19") (pin "24") (pinfunction "CVDD_24") (pintype "passive"))
      (node (ref "U19") (pin "31") (pinfunction "CVDD_31") (pintype "passive"))
      (node (ref "U19") (pin "5") (pinfunction "CVDD_5") (pintype "passive"))
      (node (ref "U19") (pin "7") (pinfunction "CVDD_7") (pintype "passive"))
    )
    (net (code "102") (name "VCC3.3") (class "Default")
      (node (ref "C32") (pin "2") (pintype "passive"))
      (node (ref "C33") (pin "2") (pintype "passive"))
      (node (ref "C36") (pin "2") (pintype "passive"))
      (node (ref "C37") (pin "2") (pintype "passive"))
      (node (ref "C52") (pin "1") (pintype "passive"))
      (node (ref "C74") (pin "1") (pintype "passive"))
      (node (ref "C75") (pin "2") (pintype "passive"))
      (node (ref "H1") (pin "4") (pinfunction "4_4") (pintype "passive"))
      (node (ref "H5") (pin "1") (pinfunction "1_1") (pintype "passive"))
      (node (ref "OLED1") (pin "11") (pinfunction "BS1_11") (pintype "passive"))
      (node (ref "OLED1") (pin "12") (pinfunction "BS2_12") (pintype "passive"))
      (node (ref "OLED1") (pin "6") (pinfunction "VBAT_6") (pintype "passive"))
      (node (ref "OLED1") (pin "9") (pinfunction "VDD_9") (pintype "passive"))
      (node (ref "R15") (pin "2") (pintype "passive"))
      (node (ref "R16") (pin "2") (pintype "passive"))
      (node (ref "R27") (pin "2") (pintype "passive"))
      (node (ref "R28") (pin "2") (pintype "passive"))
      (node (ref "R29") (pin "1") (pintype "passive"))
      (node (ref "R32") (pin "1") (pintype "passive"))
      (node (ref "R33") (pin "1") (pintype "passive"))
      (node (ref "R34") (pin "1") (pintype "passive"))
      (node (ref "R35") (pin "1") (pintype "passive"))
      (node (ref "R4") (pin "2") (pintype "passive"))
      (node (ref "R42") (pin "2") (pintype "passive"))
      (node (ref "R68") (pin "2") (pintype "passive"))
      (node (ref "TF_CARD") (pin "4") (pinfunction "VDD_4") (pintype "passive"))
      (node (ref "U19") (pin "14") (pinfunction "IOVDD_14") (pintype "passive"))
      (node (ref "U19") (pin "19") (pinfunction "IOVDD_19") (pintype "passive"))
      (node (ref "U19") (pin "32") (pinfunction "TEST_32") (pintype "passive"))
      (node (ref "U19") (pin "6") (pinfunction "IOVDD_6") (pintype "passive"))
      (node (ref "U2") (pin "5") (pinfunction "OUT_5") (pintype "passive"))
    )
    (net (code "103") (name "VUSB") (class "Default")
      (node (ref "USB") (pin "1") (pinfunction "VCC_1") (pintype "passive"))
    )
    (net (code "104") (name "unconnected-(BLE-GND-Pad5)") (class "Default")
      (node (ref "BLE") (pin "5") (pinfunction "GND_5") (pintype "passive"))
    )
    (net (code "105") (name "unconnected-(OLED1-NC(VBREF)-Pad7)") (class "Default")
      (node (ref "OLED1") (pin "7") (pinfunction "NC(VBREF)_7") (pintype "passive"))
    )
    (net (code "106") (name "unconnected-(POWER-GND-Pad4)") (class "Default")
      (node (ref "POWER") (pin "4") (pinfunction "GND_4") (pintype "passive"))
    )
    (net (code "107") (name "unconnected-(POWER-GND-Pad5)") (class "Default")
      (node (ref "POWER") (pin "5") (pinfunction "GND_5") (pintype "passive"))
    )
    (net (code "108") (name "unconnected-(POWER-I{slash}O-Pad1)") (class "Default")
      (node (ref "POWER") (pin "1") (pinfunction "I/O_1") (pintype "passive"))
    )
    (net (code "109") (name "unconnected-(TF_CARD-DAT1{slash}IRQ-Pad8)") (class "Default")
      (node (ref "TF_CARD") (pin "8") (pinfunction "DAT1/IRQ_8") (pintype "passive"))
    )
    (net (code "110") (name "unconnected-(TF_CARD-DAT2{slash}NC-Pad1)") (class "Default")
      (node (ref "TF_CARD") (pin "1") (pinfunction "DAT2/NC_1") (pintype "passive"))
    )
    (net (code "111") (name "unconnected-(U4-INB+-Pad5)") (class "Default")
      (node (ref "U4") (pin "5") (pinfunction "INB+_5") (pintype "passive"))
    )
    (net (code "112") (name "unconnected-(U4-INB--Pad6)") (class "Default")
      (node (ref "U4") (pin "6") (pinfunction "INB-_6") (pintype "passive"))
    )
    (net (code "113") (name "unconnected-(U4-OUTB-Pad7)") (class "Default")
      (node (ref "U4") (pin "7") (pinfunction "OUTB_7") (pintype "passive"))
    )
    (net (code "114") (name "unconnected-(U19-GPIO2{slash}DCLK-Pad9)") (class "Default")
      (node (ref "U19") (pin "9") (pinfunction "GPIO2/DCLK_9") (pintype "passive+no_connect"))
    )
    (net (code "115") (name "unconnected-(U19-GPIO3{slash}SDATA-Pad10)") (class "Default")
      (node (ref "U19") (pin "10") (pinfunction "GPIO3/SDATA_10") (pintype "passive+no_connect"))
    )
    (net (code "116") (name "unconnected-(U19-GPIO5{slash}I2S_MCLK-Pad25)") (class "Default")
      (node (ref "U19") (pin "25") (pinfunction "GPIO5/I2S_MCLK_25") (pintype "passive+no_connect"))
    )
    (net (code "117") (name "unconnected-(U19-GPIO6{slash}I2S_SCLK-Pad11)") (class "Default")
      (node (ref "U19") (pin "11") (pinfunction "GPIO6/I2S_SCLK_11") (pintype "passive+no_connect"))
    )
    (net (code "118") (name "unconnected-(U19-GPIO7{slash}I2S_SDATA-Pad12)") (class "Default")
      (node (ref "U19") (pin "12") (pinfunction "GPIO7/I2S_SDATA_12") (pintype "passive+no_connect"))
    )
    (net (code "119") (name "unconnected-(U19-TX-Pad27)") (class "Default")
      (node (ref "U19") (pin "27") (pinfunction "TX_27") (pintype "passive+no_connect"))
    )
    (net (code "120") (name "unconnected-(U19-VCO-Pad15)") (class "Default")
      (node (ref "U19") (pin "15") (pinfunction "VCO_15") (pintype "passive+no_connect"))
    )
    (net (code "121") (name "unconnected-(USB-ID-Pad4)") (class "Default")
      (node (ref "USB") (pin "4") (pinfunction "ID_4") (pintype "passive"))
    )
    (net (code "122") (name "unconnected-(USB-Shell1-Pad6)") (class "Default")
      (node (ref "USB") (pin "6") (pinfunction "Shell1_6") (pintype "passive"))
    )
    (net (code "123") (name "unconnected-(USB-Shell2-Pad7)") (class "Default")
      (node (ref "USB") (pin "7") (pinfunction "Shell2_7") (pintype "passive"))
    )
    (net (code "124") (name "unconnected-(USB-Shell3-Pad8)") (class "Default")
      (node (ref "USB") (pin "8") (pinfunction "Shell3_8") (pintype "passive"))
    )
    (net (code "125") (name "unconnected-(USB-Shell4-Pad9)") (class "Default")
      (node (ref "USB") (pin "9") (pinfunction "Shell4_9") (pintype "passive"))
    )
  )
)
